# Noduino-Falcon.net
KiCad netlist of a schematic drawn in EAGLE
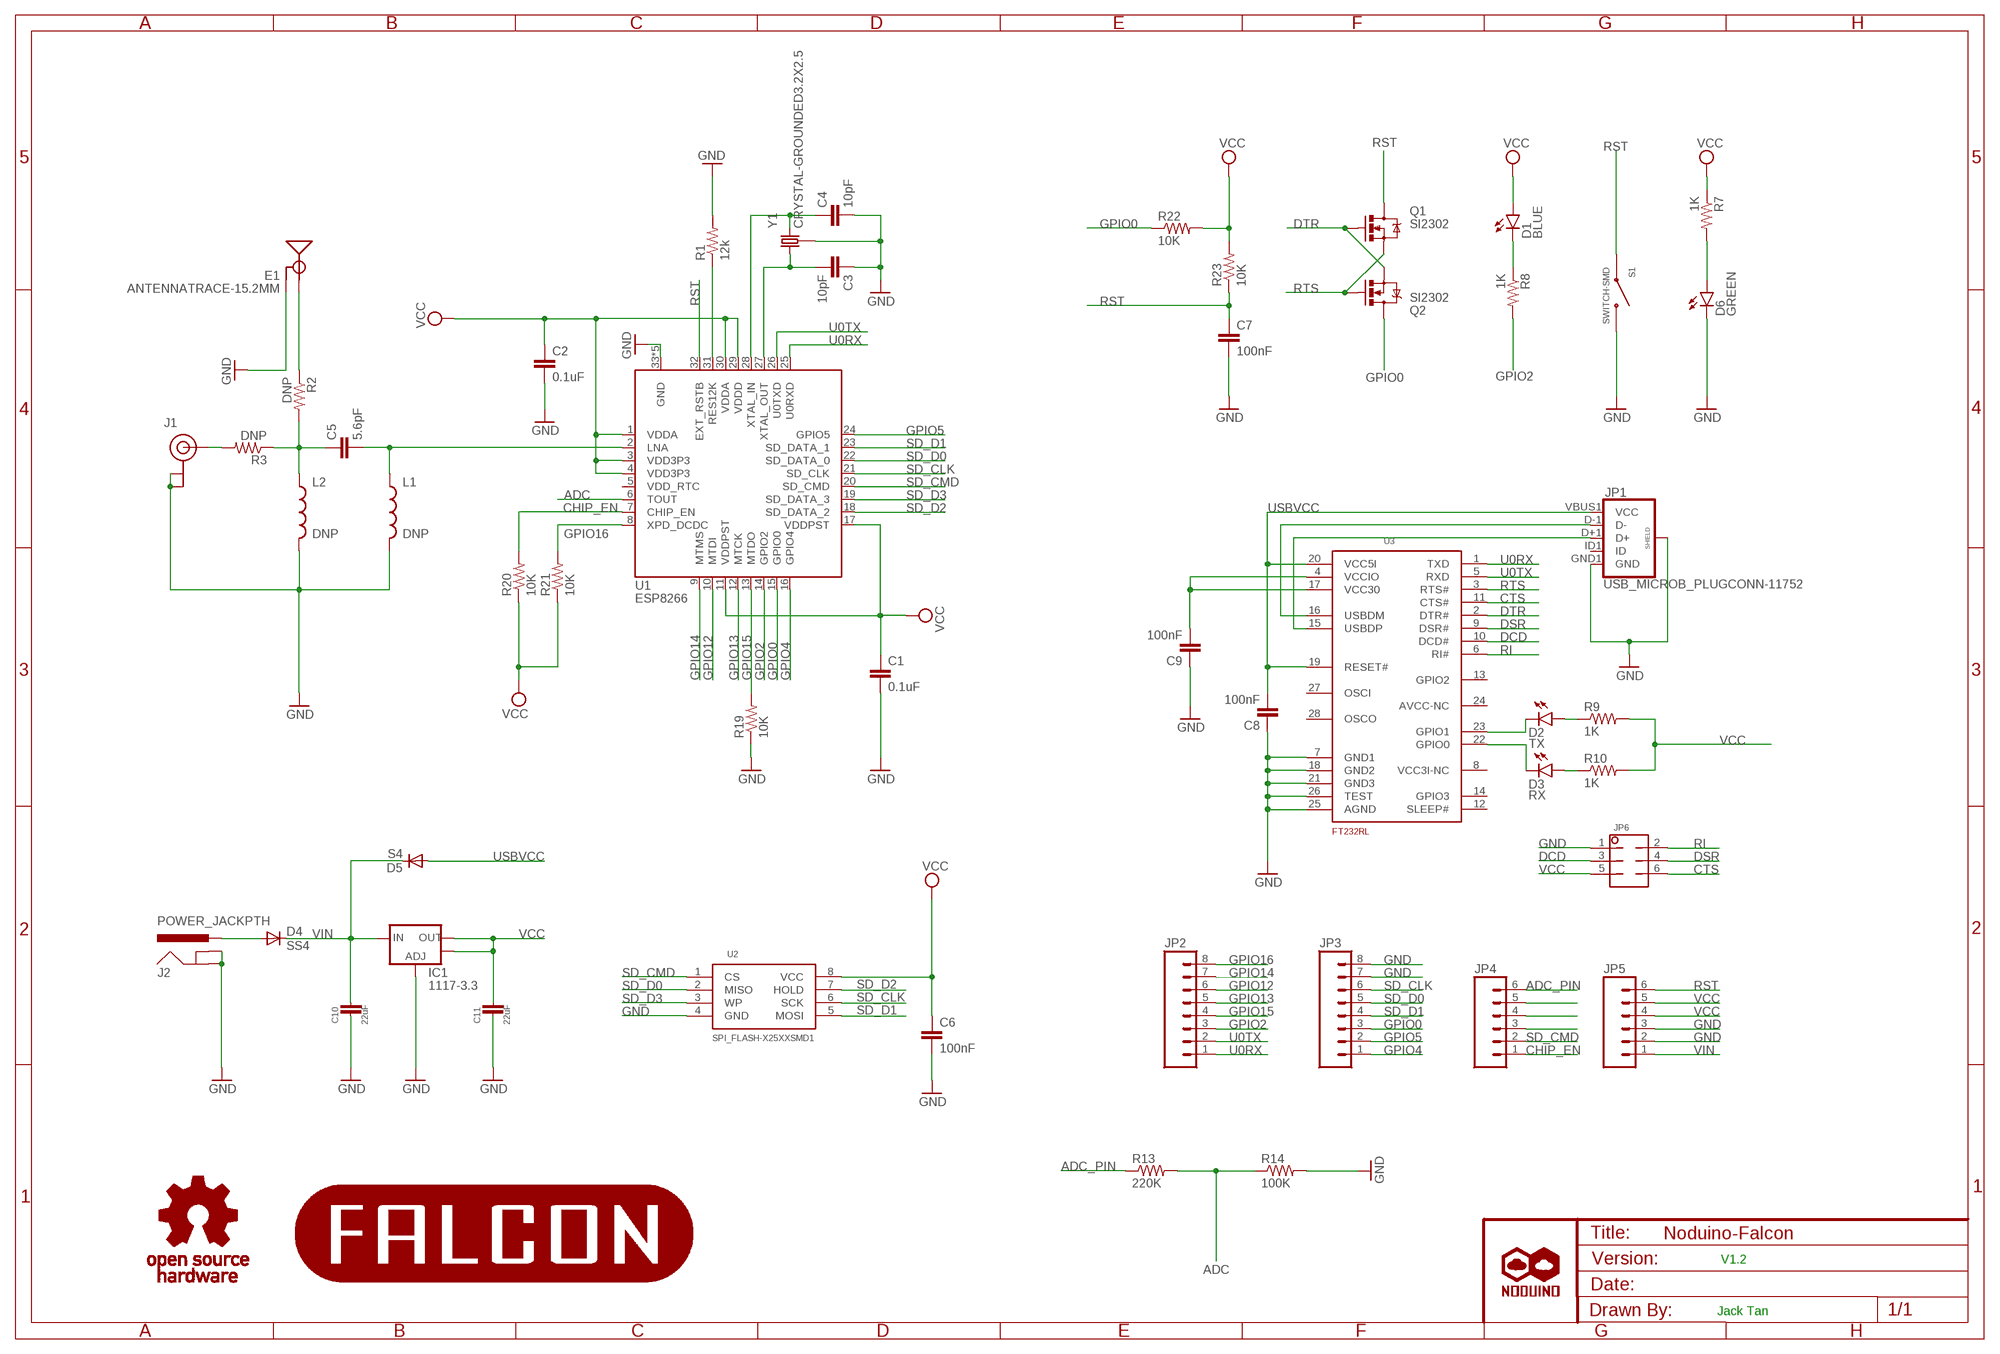
[diagram p0: schematic, sheet 1]

(export (version "E")
  (design (tool "Eeschema 10.0.6"))
  (components
    (comp (ref "C1")
      (value "0.1uF")
      (footprint "eagle-import:0603-CAP")
      (libsource (lib "eagle-import") (part "0.1UF-25V(+80/-20%)(0603)"))
    )
    (comp (ref "C2")
      (value "0.1uF")
      (footprint "eagle-import:0603-CAP")
      (libsource (lib "eagle-import") (part "0.1UF-25V(+80/-20%)(0603)"))
    )
    (comp (ref "C3")
      (value "10pF")
      (footprint "eagle-import:0603-CAP")
      (libsource (lib "eagle-import") (part "10PF-50V-5%(0603)"))
    )
    (comp (ref "C4")
      (value "10pF")
      (footprint "eagle-import:0603-CAP")
      (libsource (lib "eagle-import") (part "10PF-50V-5%(0603)"))
    )
    (comp (ref "C5")
      (value "5.6pF")
      (footprint "eagle-import:0603-CAP")
      (libsource (lib "eagle-import") (part "CAP0603-CAP"))
    )
    (comp (ref "C6")
      (value "100nF")
      (footprint "eagle-import:0603-CAP")
      (libsource (lib "eagle-import") (part "CAP0603-CAP"))
    )
    (comp (ref "C7")
      (value "100nF")
      (footprint "eagle-import:0603-CAP")
      (libsource (lib "eagle-import") (part "CAP0603-CAP"))
    )
    (comp (ref "C8")
      (value "100nF")
      (footprint "eagle-import:0603-CAP")
      (libsource (lib "eagle-import") (part "CAP0603-CAP"))
    )
    (comp (ref "C9")
      (value "100nF")
      (footprint "eagle-import:0603-CAP")
      (libsource (lib "eagle-import") (part "CAP0603-CAP"))
    )
    (comp (ref "C10")
      (value "22uF")
      (footprint "eagle-import:C1206")
      (libsource (lib "eagle-import") (part "CAP-C1206"))
    )
    (comp (ref "C11")
      (value "22uF")
      (footprint "eagle-import:C1206")
      (libsource (lib "eagle-import") (part "CAP-C1206"))
    )
    (comp (ref "D1")
      (value "BLUE")
      (footprint "eagle-import:LED-0603")
      (libsource (lib "eagle-import") (part "LED-GREEN0603"))
    )
    (comp (ref "D2")
      (value "TX")
      (footprint "eagle-import:LED-0603")
      (libsource (lib "eagle-import") (part "LED-GREEN0603"))
    )
    (comp (ref "D3")
      (value "RX")
      (footprint "eagle-import:LED-0603")
      (libsource (lib "eagle-import") (part "LED-YELLOW0603"))
    )
    (comp (ref "D4")
      (value "SS4")
      (footprint "eagle-import:SMB-DIODE")
      (libsource (lib "eagle-import") (part "DIODESMB"))
    )
    (comp (ref "D5")
      (value "S4")
      (footprint "eagle-import:SOD-323")
      (libsource (lib "eagle-import") (part "DIODESOD"))
    )
    (comp (ref "D6")
      (value "GREEN")
      (footprint "eagle-import:LED-0603")
      (libsource (lib "eagle-import") (part "LED-GREEN0603"))
    )
    (comp (ref "E1")
      (value "ANTENNATRACE-15.2MM")
      (footprint "eagle-import:TRACE_ANTENNA_2.4GHZ_15.2MM")
      (libsource (lib "eagle-import") (part "ANTENNATRACE-15.2MM"))
    )
    (comp (ref "IC1")
      (value "1117-3.3")
      (footprint "eagle-import:SOT223")
      (libsource (lib "eagle-import") (part "AMS1117SOT223"))
    )
    (comp (ref "J1")
      (value "U.FL")
      (footprint "eagle-import:U.FL")
      (libsource (lib "eagle-import") (part "U.FL"))
    )
    (comp (ref "J2")
      (value "POWER_JACKPTH")
      (footprint "eagle-import:POWER_JACK_PTH")
      (libsource (lib "eagle-import") (part "POWER_JACKPTH"))
    )
    (comp (ref "JP1")
      (value "USB_MICROB_PLUGCONN-11752")
      (footprint "eagle-import:USB-B-MICRO-SMD_V03")
      (libsource (lib "eagle-import") (part "USB_MICROB_PLUGCONN-11752"))
    )
    (comp (ref "JP2")
      (value "M081X08")
      (footprint "eagle-import:1X08")
      (libsource (lib "eagle-import") (part "M081X08"))
    )
    (comp (ref "JP3")
      (value "M081X08")
      (footprint "eagle-import:1X08")
      (libsource (lib "eagle-import") (part "M081X08"))
    )
    (comp (ref "JP4")
      (value "M06SIP")
      (footprint "eagle-import:1X06")
      (libsource (lib "eagle-import") (part "M06SIP"))
    )
    (comp (ref "JP5")
      (value "M06SIP")
      (footprint "eagle-import:1X06")
      (libsource (lib "eagle-import") (part "M06SIP"))
    )
    (comp (ref "JP6")
      (value "M02X3")
      (footprint "eagle-import:2X3")
      (libsource (lib "eagle-import") (part "M02X3"))
    )
    (comp (ref "L1")
      (value "DNP")
      (footprint "eagle-import:0603")
      (libsource (lib "eagle-import") (part "INDUCTOR0603"))
    )
    (comp (ref "L2")
      (value "DNP")
      (footprint "eagle-import:0603")
      (libsource (lib "eagle-import") (part "INDUCTOR0603"))
    )
    (comp (ref "Q1")
      (value "SI2302")
      (footprint "eagle-import:SOT23-3")
      (libsource (lib "eagle-import") (part "-MOSFET-N-SMD"))
    )
    (comp (ref "Q2")
      (value "SI2302")
      (footprint "eagle-import:SOT23-3")
      (libsource (lib "eagle-import") (part "-MOSFET-N-SMD"))
    )
    (comp (ref "R1")
      (value "12k")
      (footprint "eagle-import:0603-RES")
      (libsource (lib "eagle-import") (part "12KOHM-1/10W-1%(0603)"))
    )
    (comp (ref "R2")
      (value "DNP")
      (footprint "eagle-import:0603-RES")
      (libsource (lib "eagle-import") (part "RESISTOR0603-RES"))
    )
    (comp (ref "R3")
      (value "DNP")
      (footprint "eagle-import:0603-RES")
      (libsource (lib "eagle-import") (part "RESISTOR0603-RES"))
    )
    (comp (ref "R7")
      (value "1K")
      (footprint "eagle-import:0603-RES")
      (libsource (lib "eagle-import") (part "RESISTOR0603-RES"))
    )
    (comp (ref "R8")
      (value "1K")
      (footprint "eagle-import:0603-RES")
      (libsource (lib "eagle-import") (part "RESISTOR0603-RES"))
    )
    (comp (ref "R9")
      (value "1K")
      (footprint "eagle-import:0603-RES")
      (libsource (lib "eagle-import") (part "RESISTOR0603-RES"))
    )
    (comp (ref "R10")
      (value "1K")
      (footprint "eagle-import:0603-RES")
      (libsource (lib "eagle-import") (part "RESISTOR0603-RES"))
    )
    (comp (ref "R13")
      (value "220K")
      (footprint "eagle-import:0603-RES")
      (libsource (lib "eagle-import") (part "RESISTOR0603-RES"))
    )
    (comp (ref "R14")
      (value "100K")
      (footprint "eagle-import:0603-RES")
      (libsource (lib "eagle-import") (part "RESISTOR0603-RES"))
    )
    (comp (ref "R19")
      (value "10K")
      (footprint "eagle-import:0603-RES")
      (libsource (lib "eagle-import") (part "RESISTOR0603-RES"))
    )
    (comp (ref "R20")
      (value "10K")
      (footprint "eagle-import:0603-RES")
      (libsource (lib "eagle-import") (part "10KOHM1/10W1%(0603)0603"))
    )
    (comp (ref "R21")
      (value "10K")
      (footprint "eagle-import:0603-RES")
      (libsource (lib "eagle-import") (part "10KOHM1/10W1%(0603)0603"))
    )
    (comp (ref "R22")
      (value "10K")
      (footprint "eagle-import:0603-RES")
      (libsource (lib "eagle-import") (part "RESISTOR0603-RES"))
    )
    (comp (ref "R23")
      (value "10K")
      (footprint "eagle-import:0603-RES")
      (libsource (lib "eagle-import") (part "RESISTOR0603-RES"))
    )
    (comp (ref "S1")
      (value "SWITCH-SMD")
      (footprint "eagle-import:TACTILE-SWITCH-1101NE")
      (libsource (lib "eagle-import") (part "SWITCH-SMD"))
    )
    (comp (ref "U$1")
      (value "NODUINO-LOGO-ALL")
      (footprint "eagle-import:NODUINO-ALL-1")
      (libsource (lib "eagle-import") (part "NODUINO-LOGO-ALL"))
    )
    (comp (ref "U$2")
      (value "NODUINO-FALCON")
      (footprint "eagle-import:NODUINO-FALCON")
      (libsource (lib "eagle-import") (part "NODUINO-FALCON"))
    )
    (comp (ref "U$3")
      (value "OPEN_HARDWARE_LOGO")
      (footprint "eagle-import:OPEN_HARDWARE_LOGO")
      (libsource (lib "eagle-import") (part "OPEN_HARDWARE_LOGO"))
    )
    (comp (ref "U1")
      (value "ESP8266")
      (footprint "eagle-import:QFN-32")
      (libsource (lib "eagle-import") (part "ESP8266"))
    )
    (comp (ref "U2")
      (value "SPI_FLASH-X25XXSMD1")
      (footprint "eagle-import:SO08-EIAJ")
      (libsource (lib "eagle-import") (part "SPI_FLASH-X25XXSMD1"))
    )
    (comp (ref "U3")
      (value "FT232RL")
      (footprint "eagle-import:SSOP28")
      (libsource (lib "eagle-import") (part "FT232RL"))
    )
    (comp (ref "Y1")
      (value "CRYSTAL-GROUNDED3.2X2.5")
      (footprint "eagle-import:CRYSTAL-SMD-3.2X2.5")
      (libsource (lib "eagle-import") (part "CRYSTAL-GROUNDED3.2X2.5"))
    )
  )
  (nets
    (net (code "1") (name "/ADC") (class "Default")
      (node (ref "R13") (pin "2") (pinfunction "2_2") (pintype "passive"))
      (node (ref "R14") (pin "1") (pinfunction "1_1") (pintype "passive"))
      (node (ref "U1") (pin "6") (pinfunction "TOUT_6") (pintype "bidirectional"))
    )
    (net (code "2") (name "/ADC_PIN") (class "Default")
      (node (ref "JP4") (pin "6") (pinfunction "6_6") (pintype "passive"))
      (node (ref "R13") (pin "1") (pinfunction "1_1") (pintype "passive"))
    )
    (net (code "3") (name "/CHIP_EN") (class "Default")
      (node (ref "JP4") (pin "1") (pinfunction "1_1") (pintype "passive"))
      (node (ref "R20") (pin "2") (pinfunction "2_2") (pintype "passive"))
      (node (ref "U1") (pin "7") (pinfunction "CHIP_EN_7") (pintype "bidirectional"))
    )
    (net (code "4") (name "/CTS") (class "Default")
      (node (ref "JP6") (pin "6") (pinfunction "6_6") (pintype "bidirectional"))
      (node (ref "U3") (pin "11") (pinfunction "CTS#_11") (pintype "bidirectional"))
    )
    (net (code "5") (name "/DCD") (class "Default")
      (node (ref "JP6") (pin "3") (pinfunction "3_3") (pintype "bidirectional"))
      (node (ref "U3") (pin "10") (pinfunction "DCD#_10") (pintype "bidirectional"))
    )
    (net (code "6") (name "/DSR") (class "Default")
      (node (ref "JP6") (pin "4") (pinfunction "4_4") (pintype "bidirectional"))
      (node (ref "U3") (pin "9") (pinfunction "DSR#_9") (pintype "bidirectional"))
    )
    (net (code "7") (name "/DTR") (class "Default")
      (node (ref "Q1") (pin "1") (pinfunction "G_1") (pintype "passive"))
      (node (ref "Q2") (pin "2") (pinfunction "S_2") (pintype "passive"))
      (node (ref "U3") (pin "2") (pinfunction "DTR#_2") (pintype "bidirectional"))
    )
    (net (code "8") (name "/GPIO0") (class "Default")
      (node (ref "JP3") (pin "3") (pinfunction "3_3") (pintype "passive"))
      (node (ref "Q2") (pin "3") (pinfunction "D_3") (pintype "passive"))
      (node (ref "R22") (pin "1") (pinfunction "1_1") (pintype "passive"))
      (node (ref "U1") (pin "15") (pinfunction "GPIO0_15") (pintype "bidirectional"))
    )
    (net (code "9") (name "/GPIO2") (class "Default")
      (node (ref "JP2") (pin "3") (pinfunction "3_3") (pintype "passive"))
      (node (ref "R8") (pin "2") (pinfunction "2_2") (pintype "passive"))
      (node (ref "U1") (pin "14") (pinfunction "GPIO2_14") (pintype "bidirectional"))
    )
    (net (code "10") (name "/GPIO4") (class "Default")
      (node (ref "JP3") (pin "1") (pinfunction "1_1") (pintype "passive"))
      (node (ref "U1") (pin "16") (pinfunction "GPIO4_16") (pintype "bidirectional"))
    )
    (net (code "11") (name "/GPIO5") (class "Default")
      (node (ref "JP3") (pin "2") (pinfunction "2_2") (pintype "passive"))
      (node (ref "U1") (pin "24") (pinfunction "GPIO5_24") (pintype "bidirectional"))
    )
    (net (code "12") (name "/GPIO12") (class "Default")
      (node (ref "JP2") (pin "6") (pinfunction "6_6") (pintype "passive"))
      (node (ref "U1") (pin "10") (pinfunction "MTDI_10") (pintype "bidirectional"))
    )
    (net (code "13") (name "/GPIO13") (class "Default")
      (node (ref "JP2") (pin "5") (pinfunction "5_5") (pintype "passive"))
      (node (ref "U1") (pin "12") (pinfunction "MTCK_12") (pintype "bidirectional"))
    )
    (net (code "14") (name "/GPIO14") (class "Default")
      (node (ref "JP2") (pin "7") (pinfunction "7_7") (pintype "passive"))
      (node (ref "U1") (pin "9") (pinfunction "MTMS_9") (pintype "bidirectional"))
    )
    (net (code "15") (name "/GPIO15") (class "Default")
      (node (ref "JP2") (pin "4") (pinfunction "4_4") (pintype "passive"))
      (node (ref "R19") (pin "2") (pinfunction "2_2") (pintype "passive"))
      (node (ref "U1") (pin "13") (pinfunction "MTDO_13") (pintype "bidirectional"))
    )
    (net (code "16") (name "/GPIO16") (class "Default")
      (node (ref "JP2") (pin "8") (pinfunction "8_8") (pintype "passive"))
      (node (ref "R21") (pin "2") (pinfunction "2_2") (pintype "passive"))
      (node (ref "U1") (pin "8") (pinfunction "XPD_DCDC_8") (pintype "bidirectional"))
    )
    (net (code "17") (name "/RI") (class "Default")
      (node (ref "JP6") (pin "2") (pinfunction "2_2") (pintype "bidirectional"))
      (node (ref "U3") (pin "6") (pinfunction "RI#_6") (pintype "bidirectional"))
    )
    (net (code "18") (name "/RST") (class "Default")
      (node (ref "C7") (pin "1") (pinfunction "1_1") (pintype "passive"))
      (node (ref "JP5") (pin "6") (pinfunction "6_6") (pintype "passive"))
      (node (ref "Q1") (pin "3") (pinfunction "D_3") (pintype "passive"))
      (node (ref "R23") (pin "1") (pinfunction "1_1") (pintype "passive"))
      (node (ref "S1") (pin "P$2") (pinfunction "2_P$2") (pintype "bidirectional"))
      (node (ref "U1") (pin "32") (pinfunction "EXT_RSTB_32") (pintype "bidirectional"))
    )
    (net (code "19") (name "/RTS") (class "Default")
      (node (ref "Q1") (pin "2") (pinfunction "S_2") (pintype "passive"))
      (node (ref "Q2") (pin "1") (pinfunction "G_1") (pintype "passive"))
      (node (ref "U3") (pin "3") (pinfunction "RTS#_3") (pintype "bidirectional"))
    )
    (net (code "20") (name "/SD_CLK") (class "Default")
      (node (ref "JP3") (pin "6") (pinfunction "6_6") (pintype "passive"))
      (node (ref "U1") (pin "21") (pinfunction "SD_CLK_21") (pintype "bidirectional"))
      (node (ref "U2") (pin "6") (pinfunction "SCK_6") (pintype "bidirectional"))
    )
    (net (code "21") (name "/SD_CMD") (class "Default")
      (node (ref "JP4") (pin "2") (pinfunction "2_2") (pintype "passive"))
      (node (ref "U1") (pin "20") (pinfunction "SD_CMD_20") (pintype "bidirectional"))
      (node (ref "U2") (pin "1") (pinfunction "CS_1") (pintype "bidirectional"))
    )
    (net (code "22") (name "/SD_D0") (class "Default")
      (node (ref "JP3") (pin "5") (pinfunction "5_5") (pintype "passive"))
      (node (ref "U1") (pin "22") (pinfunction "SD_DATA_0_22") (pintype "bidirectional"))
      (node (ref "U2") (pin "2") (pinfunction "MISO_2") (pintype "bidirectional"))
    )
    (net (code "23") (name "/SD_D1") (class "Default")
      (node (ref "JP3") (pin "4") (pinfunction "4_4") (pintype "passive"))
      (node (ref "U1") (pin "23") (pinfunction "SD_DATA_1_23") (pintype "bidirectional"))
      (node (ref "U2") (pin "5") (pinfunction "MOSI_5") (pintype "bidirectional"))
    )
    (net (code "24") (name "/SD_D2") (class "Default")
      (node (ref "U1") (pin "18") (pinfunction "SD_DATA_2_18") (pintype "bidirectional"))
      (node (ref "U2") (pin "7") (pinfunction "HOLD_7") (pintype "bidirectional"))
    )
    (net (code "25") (name "/SD_D3") (class "Default")
      (node (ref "U1") (pin "19") (pinfunction "SD_DATA_3_19") (pintype "bidirectional"))
      (node (ref "U2") (pin "3") (pinfunction "WP_3") (pintype "bidirectional"))
    )
    (net (code "26") (name "/U0RX") (class "Default")
      (node (ref "JP2") (pin "1") (pinfunction "1_1") (pintype "passive"))
      (node (ref "U1") (pin "25") (pinfunction "U0RXD_25") (pintype "bidirectional"))
      (node (ref "U3") (pin "1") (pinfunction "TXD_1") (pintype "bidirectional"))
    )
    (net (code "27") (name "/U0TX") (class "Default")
      (node (ref "JP2") (pin "2") (pinfunction "2_2") (pintype "passive"))
      (node (ref "U1") (pin "26") (pinfunction "U0TXD_26") (pintype "bidirectional"))
      (node (ref "U3") (pin "5") (pinfunction "RXD_5") (pintype "bidirectional"))
    )
    (net (code "28") (name "/USBVCC") (class "Default")
      (node (ref "C8") (pin "2") (pinfunction "2_2") (pintype "passive"))
      (node (ref "D5") (pin "2") (pinfunction "A_2") (pintype "passive"))
      (node (ref "JP1") (pin "VBUS1") (pinfunction "VCC_VBUS1") (pintype "bidirectional"))
      (node (ref "U3") (pin "19") (pinfunction "RESET#_19") (pintype "bidirectional"))
      (node (ref "U3") (pin "20") (pinfunction "VCC5I_20") (pintype "bidirectional"))
    )
    (net (code "29") (name "/VIN") (class "Default")
      (node (ref "C10") (pin "1") (pinfunction "1_1") (pintype "passive"))
      (node (ref "D4") (pin "C") (pinfunction "C_C") (pintype "passive"))
      (node (ref "D5") (pin "1") (pinfunction "C_1") (pintype "passive"))
      (node (ref "IC1") (pin "3") (pinfunction "IN_3") (pintype "input"))
      (node (ref "JP5") (pin "1") (pinfunction "1_1") (pintype "passive"))
    )
    (net (code "30") (name "GND") (class "Default")
      (node (ref "C1") (pin "2") (pinfunction "2_2") (pintype "passive"))
      (node (ref "C10") (pin "2") (pinfunction "2_2") (pintype "passive"))
      (node (ref "C11") (pin "2") (pinfunction "2_2") (pintype "passive"))
      (node (ref "C2") (pin "2") (pinfunction "2_2") (pintype "passive"))
      (node (ref "C3") (pin "1") (pinfunction "1_1") (pintype "passive"))
      (node (ref "C4") (pin "2") (pinfunction "2_2") (pintype "passive"))
      (node (ref "C6") (pin "2") (pinfunction "2_2") (pintype "passive"))
      (node (ref "C7") (pin "2") (pinfunction "2_2") (pintype "passive"))
      (node (ref "C8") (pin "1") (pinfunction "1_1") (pintype "passive"))
      (node (ref "C9") (pin "1") (pinfunction "1_1") (pintype "passive"))
      (node (ref "D6") (pin "C") (pinfunction "C_C") (pintype "passive"))
      (node (ref "E1") (pin "GND") (pinfunction "GND_GND") (pintype "bidirectional"))
      (node (ref "IC1") (pin "1") (pinfunction "ADJ_1") (pintype "input"))
      (node (ref "J1") (pin "P$1") (pinfunction "GND_P$1") (pintype "bidirectional"))
      (node (ref "J1") (pin "P$2") (pinfunction "GND_P$2") (pintype "bidirectional"))
      (node (ref "J2") (pin "GND") (pinfunction "GND_GND") (pintype "bidirectional"))
      (node (ref "J2") (pin "GNDBREAK") (pinfunction "GNDBREAK_GNDBREAK") (pintype "bidirectional"))
      (node (ref "JP1") (pin "GND1") (pinfunction "GND_GND1") (pintype "bidirectional"))
      (node (ref "JP1") (pin "SHIELD1") (pinfunction "SHIELD_SHIELD1") (pintype "bidirectional"))
      (node (ref "JP1") (pin "SHIELD2") (pinfunction "SHIELD_SHIELD2") (pintype "bidirectional"))
      (node (ref "JP1") (pin "SHIELD3") (pinfunction "SHIELD_SHIELD3") (pintype "bidirectional"))
      (node (ref "JP3") (pin "7") (pinfunction "7_7") (pintype "passive"))
      (node (ref "JP3") (pin "8") (pinfunction "8_8") (pintype "passive"))
      (node (ref "JP5") (pin "2") (pinfunction "2_2") (pintype "passive"))
      (node (ref "JP5") (pin "3") (pinfunction "3_3") (pintype "passive"))
      (node (ref "JP6") (pin "1") (pinfunction "1_1") (pintype "bidirectional"))
      (node (ref "L1") (pin "2") (pinfunction "2_2") (pintype "passive"))
      (node (ref "L2") (pin "2") (pinfunction "2_2") (pintype "passive"))
      (node (ref "R1") (pin "2") (pinfunction "2_2") (pintype "passive"))
      (node (ref "R14") (pin "2") (pinfunction "2_2") (pintype "passive"))
      (node (ref "R19") (pin "1") (pinfunction "1_1") (pintype "passive"))
      (node (ref "S1") (pin "P$1") (pinfunction "1_P$1") (pintype "bidirectional"))
      (node (ref "U1") (pin "33") (pinfunction "GND_33") (pintype "bidirectional"))
      (node (ref "U1") (pin "34") (pinfunction "GND_34") (pintype "bidirectional"))
      (node (ref "U1") (pin "35") (pinfunction "GND_35") (pintype "bidirectional"))
      (node (ref "U1") (pin "36") (pinfunction "GND_36") (pintype "bidirectional"))
      (node (ref "U1") (pin "37") (pinfunction "GND_37") (pintype "bidirectional"))
      (node (ref "U2") (pin "4") (pinfunction "GND_4") (pintype "bidirectional"))
      (node (ref "U3") (pin "18") (pinfunction "GND2_18") (pintype "bidirectional"))
      (node (ref "U3") (pin "21") (pinfunction "GND3_21") (pintype "bidirectional"))
      (node (ref "U3") (pin "25") (pinfunction "AGND_25") (pintype "bidirectional"))
      (node (ref "U3") (pin "26") (pinfunction "TEST_26") (pintype "bidirectional"))
      (node (ref "U3") (pin "7") (pinfunction "GND1_7") (pintype "bidirectional"))
      (node (ref "Y1") (pin "2") (pinfunction "GND_2") (pintype "passive"))
      (node (ref "Y1") (pin "4") (pinfunction "GND_4") (pintype "passive"))
    )
    (net (code "31") (name "Net-(C5-Pad1)") (class "Default")
      (node (ref "C5") (pin "1") (pinfunction "1_1") (pintype "passive"))
      (node (ref "L2") (pin "1") (pinfunction "1_1") (pintype "passive"))
      (node (ref "R2") (pin "2") (pinfunction "2_2") (pintype "passive"))
      (node (ref "R3") (pin "1") (pinfunction "1_1") (pintype "passive"))
    )
    (net (code "32") (name "Net-(D1-PadC)") (class "Default")
      (node (ref "D1") (pin "C") (pinfunction "C_C") (pintype "passive"))
      (node (ref "R8") (pin "1") (pinfunction "1_1") (pintype "passive"))
    )
    (net (code "33") (name "Net-(D2-PadA)") (class "Default")
      (node (ref "D2") (pin "A") (pinfunction "A_A") (pintype "passive"))
      (node (ref "R9") (pin "1") (pinfunction "1_1") (pintype "passive"))
    )
    (net (code "34") (name "Net-(D3-PadA)") (class "Default")
      (node (ref "D3") (pin "A") (pinfunction "A_A") (pintype "passive"))
      (node (ref "R10") (pin "1") (pinfunction "1_1") (pintype "passive"))
    )
    (net (code "35") (name "Net-(D4-PadA)") (class "Default")
      (node (ref "D4") (pin "A") (pinfunction "A_A") (pintype "passive"))
      (node (ref "J2") (pin "PWR") (pinfunction "PWR_PWR") (pintype "bidirectional"))
    )
    (net (code "36") (name "Net-(D6-PadA)") (class "Default")
      (node (ref "D6") (pin "A") (pinfunction "A_A") (pintype "passive"))
      (node (ref "R7") (pin "2") (pinfunction "2_2") (pintype "passive"))
    )
    (net (code "37") (name "Net-(E1-SIGNAL)") (class "Default")
      (node (ref "E1") (pin "ANT") (pinfunction "SIGNAL_ANT") (pintype "bidirectional"))
      (node (ref "R2") (pin "1") (pinfunction "1_1") (pintype "passive"))
    )
    (net (code "38") (name "Net-(J1-SIGNAL)") (class "Default")
      (node (ref "J1") (pin "P$3") (pinfunction "SIGNAL_P$3") (pintype "bidirectional"))
      (node (ref "R3") (pin "2") (pinfunction "2_2") (pintype "passive"))
    )
    (net (code "39") (name "Net-(JP1-D+)") (class "Default")
      (node (ref "JP1") (pin "D+1") (pinfunction "D+_D+1") (pintype "bidirectional"))
      (node (ref "U3") (pin "15") (pinfunction "USBDP_15") (pintype "bidirectional"))
    )
    (net (code "40") (name "Net-(JP1-D-)") (class "Default")
      (node (ref "JP1") (pin "D-1") (pinfunction "D-_D-1") (pintype "bidirectional"))
      (node (ref "U3") (pin "16") (pinfunction "USBDM_16") (pintype "bidirectional"))
    )
    (net (code "41") (name "Net-(U1-LNA)") (class "Default")
      (node (ref "C5") (pin "2") (pinfunction "2_2") (pintype "passive"))
      (node (ref "L1") (pin "1") (pinfunction "1_1") (pintype "passive"))
      (node (ref "U1") (pin "2") (pinfunction "LNA_2") (pintype "bidirectional"))
    )
    (net (code "42") (name "Net-(U1-RES12K)") (class "Default")
      (node (ref "R1") (pin "1") (pinfunction "1_1") (pintype "passive"))
      (node (ref "U1") (pin "31") (pinfunction "RES12K_31") (pintype "bidirectional"))
    )
    (net (code "43") (name "Net-(U1-XTAL_IN)") (class "Default")
      (node (ref "C4") (pin "1") (pinfunction "1_1") (pintype "passive"))
      (node (ref "U1") (pin "28") (pinfunction "XTAL_IN_28") (pintype "bidirectional"))
      (node (ref "Y1") (pin "3") (pinfunction "2_3") (pintype "passive"))
    )
    (net (code "44") (name "Net-(U1-XTAL_OUT)") (class "Default")
      (node (ref "C3") (pin "2") (pinfunction "2_2") (pintype "passive"))
      (node (ref "U1") (pin "27") (pinfunction "XTAL_OUT_27") (pintype "bidirectional"))
      (node (ref "Y1") (pin "1") (pinfunction "1_1") (pintype "passive"))
    )
    (net (code "45") (name "Net-(U3-GPIO0)") (class "Default")
      (node (ref "D3") (pin "C") (pinfunction "C_C") (pintype "passive"))
      (node (ref "U3") (pin "22") (pinfunction "GPIO0_22") (pintype "bidirectional"))
    )
    (net (code "46") (name "Net-(U3-GPIO1)") (class "Default")
      (node (ref "D2") (pin "C") (pinfunction "C_C") (pintype "passive"))
      (node (ref "U3") (pin "23") (pinfunction "GPIO1_23") (pintype "bidirectional"))
    )
    (net (code "47") (name "Net-(U3-VCC30)") (class "Default")
      (node (ref "C9") (pin "2") (pinfunction "2_2") (pintype "passive"))
      (node (ref "U3") (pin "17") (pinfunction "VCC30_17") (pintype "bidirectional"))
      (node (ref "U3") (pin "4") (pinfunction "VCCIO_4") (pintype "bidirectional"))
    )
    (net (code "48") (name "VCC") (class "Default")
      (node (ref "C1") (pin "1") (pinfunction "1_1") (pintype "passive"))
      (node (ref "C11") (pin "1") (pinfunction "1_1") (pintype "passive"))
      (node (ref "C2") (pin "1") (pinfunction "1_1") (pintype "passive"))
      (node (ref "C6") (pin "1") (pinfunction "1_1") (pintype "passive"))
      (node (ref "D1") (pin "A") (pinfunction "A_A") (pintype "passive"))
      (node (ref "IC1") (pin "2") (pinfunction "OUT_2") (pintype "bidirectional"))
      (node (ref "IC1") (pin "4") (pinfunction "OUT_4") (pintype "bidirectional"))
      (node (ref "JP5") (pin "4") (pinfunction "4_4") (pintype "passive"))
      (node (ref "JP5") (pin "5") (pinfunction "5_5") (pintype "passive"))
      (node (ref "JP6") (pin "5") (pinfunction "5_5") (pintype "bidirectional"))
      (node (ref "R10") (pin "2") (pinfunction "2_2") (pintype "passive"))
      (node (ref "R20") (pin "1") (pinfunction "1_1") (pintype "passive"))
      (node (ref "R21") (pin "1") (pinfunction "1_1") (pintype "passive"))
      (node (ref "R22") (pin "2") (pinfunction "2_2") (pintype "passive"))
      (node (ref "R23") (pin "2") (pinfunction "2_2") (pintype "passive"))
      (node (ref "R7") (pin "1") (pinfunction "1_1") (pintype "passive"))
      (node (ref "R9") (pin "2") (pinfunction "2_2") (pintype "passive"))
      (node (ref "U1") (pin "1") (pinfunction "VDDA_1") (pintype "bidirectional"))
      (node (ref "U1") (pin "11") (pinfunction "VDDPST_11") (pintype "bidirectional"))
      (node (ref "U1") (pin "17") (pinfunction "VDDPST_17") (pintype "bidirectional"))
      (node (ref "U1") (pin "29") (pinfunction "VDDD_29") (pintype "bidirectional"))
      (node (ref "U1") (pin "3") (pinfunction "VDD3P3_3") (pintype "bidirectional"))
      (node (ref "U1") (pin "30") (pinfunction "VDDA_30") (pintype "bidirectional"))
      (node (ref "U1") (pin "4") (pinfunction "VDD3P3_4") (pintype "bidirectional"))
      (node (ref "U2") (pin "8") (pinfunction "VCC_8") (pintype "bidirectional"))
    )
    (net (code "49") (name "unconnected-(JP1-ID-PadID1)") (class "Default")
      (node (ref "JP1") (pin "ID1") (pinfunction "ID_ID1") (pintype "bidirectional"))
    )
    (net (code "50") (name "unconnected-(JP4-Pad3)") (class "Default")
      (node (ref "JP4") (pin "3") (pinfunction "3_3") (pintype "passive"))
    )
    (net (code "51") (name "unconnected-(JP4-Pad4)") (class "Default")
      (node (ref "JP4") (pin "4") (pinfunction "4_4") (pintype "passive"))
    )
    (net (code "52") (name "unconnected-(JP4-Pad5)") (class "Default")
      (node (ref "JP4") (pin "5") (pinfunction "5_5") (pintype "passive"))
    )
    (net (code "53") (name "unconnected-(U1-VDD_RTC-Pad5)") (class "Default")
      (node (ref "U1") (pin "5") (pinfunction "VDD_RTC_5") (pintype "bidirectional"))
    )
    (net (code "54") (name "unconnected-(U3-AVCC-NC-Pad24)") (class "Default")
      (node (ref "U3") (pin "24") (pinfunction "AVCC-NC_24") (pintype "no_connect"))
    )
    (net (code "55") (name "unconnected-(U3-GPIO2-Pad13)") (class "Default")
      (node (ref "U3") (pin "13") (pinfunction "GPIO2_13") (pintype "bidirectional"))
    )
    (net (code "56") (name "unconnected-(U3-GPIO3-Pad14)") (class "Default")
      (node (ref "U3") (pin "14") (pinfunction "GPIO3_14") (pintype "bidirectional"))
    )
    (net (code "57") (name "unconnected-(U3-OSCI-Pad27)") (class "Default")
      (node (ref "U3") (pin "27") (pinfunction "OSCI_27") (pintype "bidirectional"))
    )
    (net (code "58") (name "unconnected-(U3-OSCO-Pad28)") (class "Default")
      (node (ref "U3") (pin "28") (pinfunction "OSCO_28") (pintype "bidirectional"))
    )
    (net (code "59") (name "unconnected-(U3-SLEEP#-Pad12)") (class "Default")
      (node (ref "U3") (pin "12") (pinfunction "SLEEP#_12") (pintype "bidirectional"))
    )
    (net (code "60") (name "unconnected-(U3-VCC3I-NC-Pad8)") (class "Default")
      (node (ref "U3") (pin "8") (pinfunction "VCC3I-NC_8") (pintype "no_connect"))
    )
  )
)
